# EVB-NORA-B2_SCHEM_0001_Power.net
KiCad netlist of a schematic drawn in Altium Designer
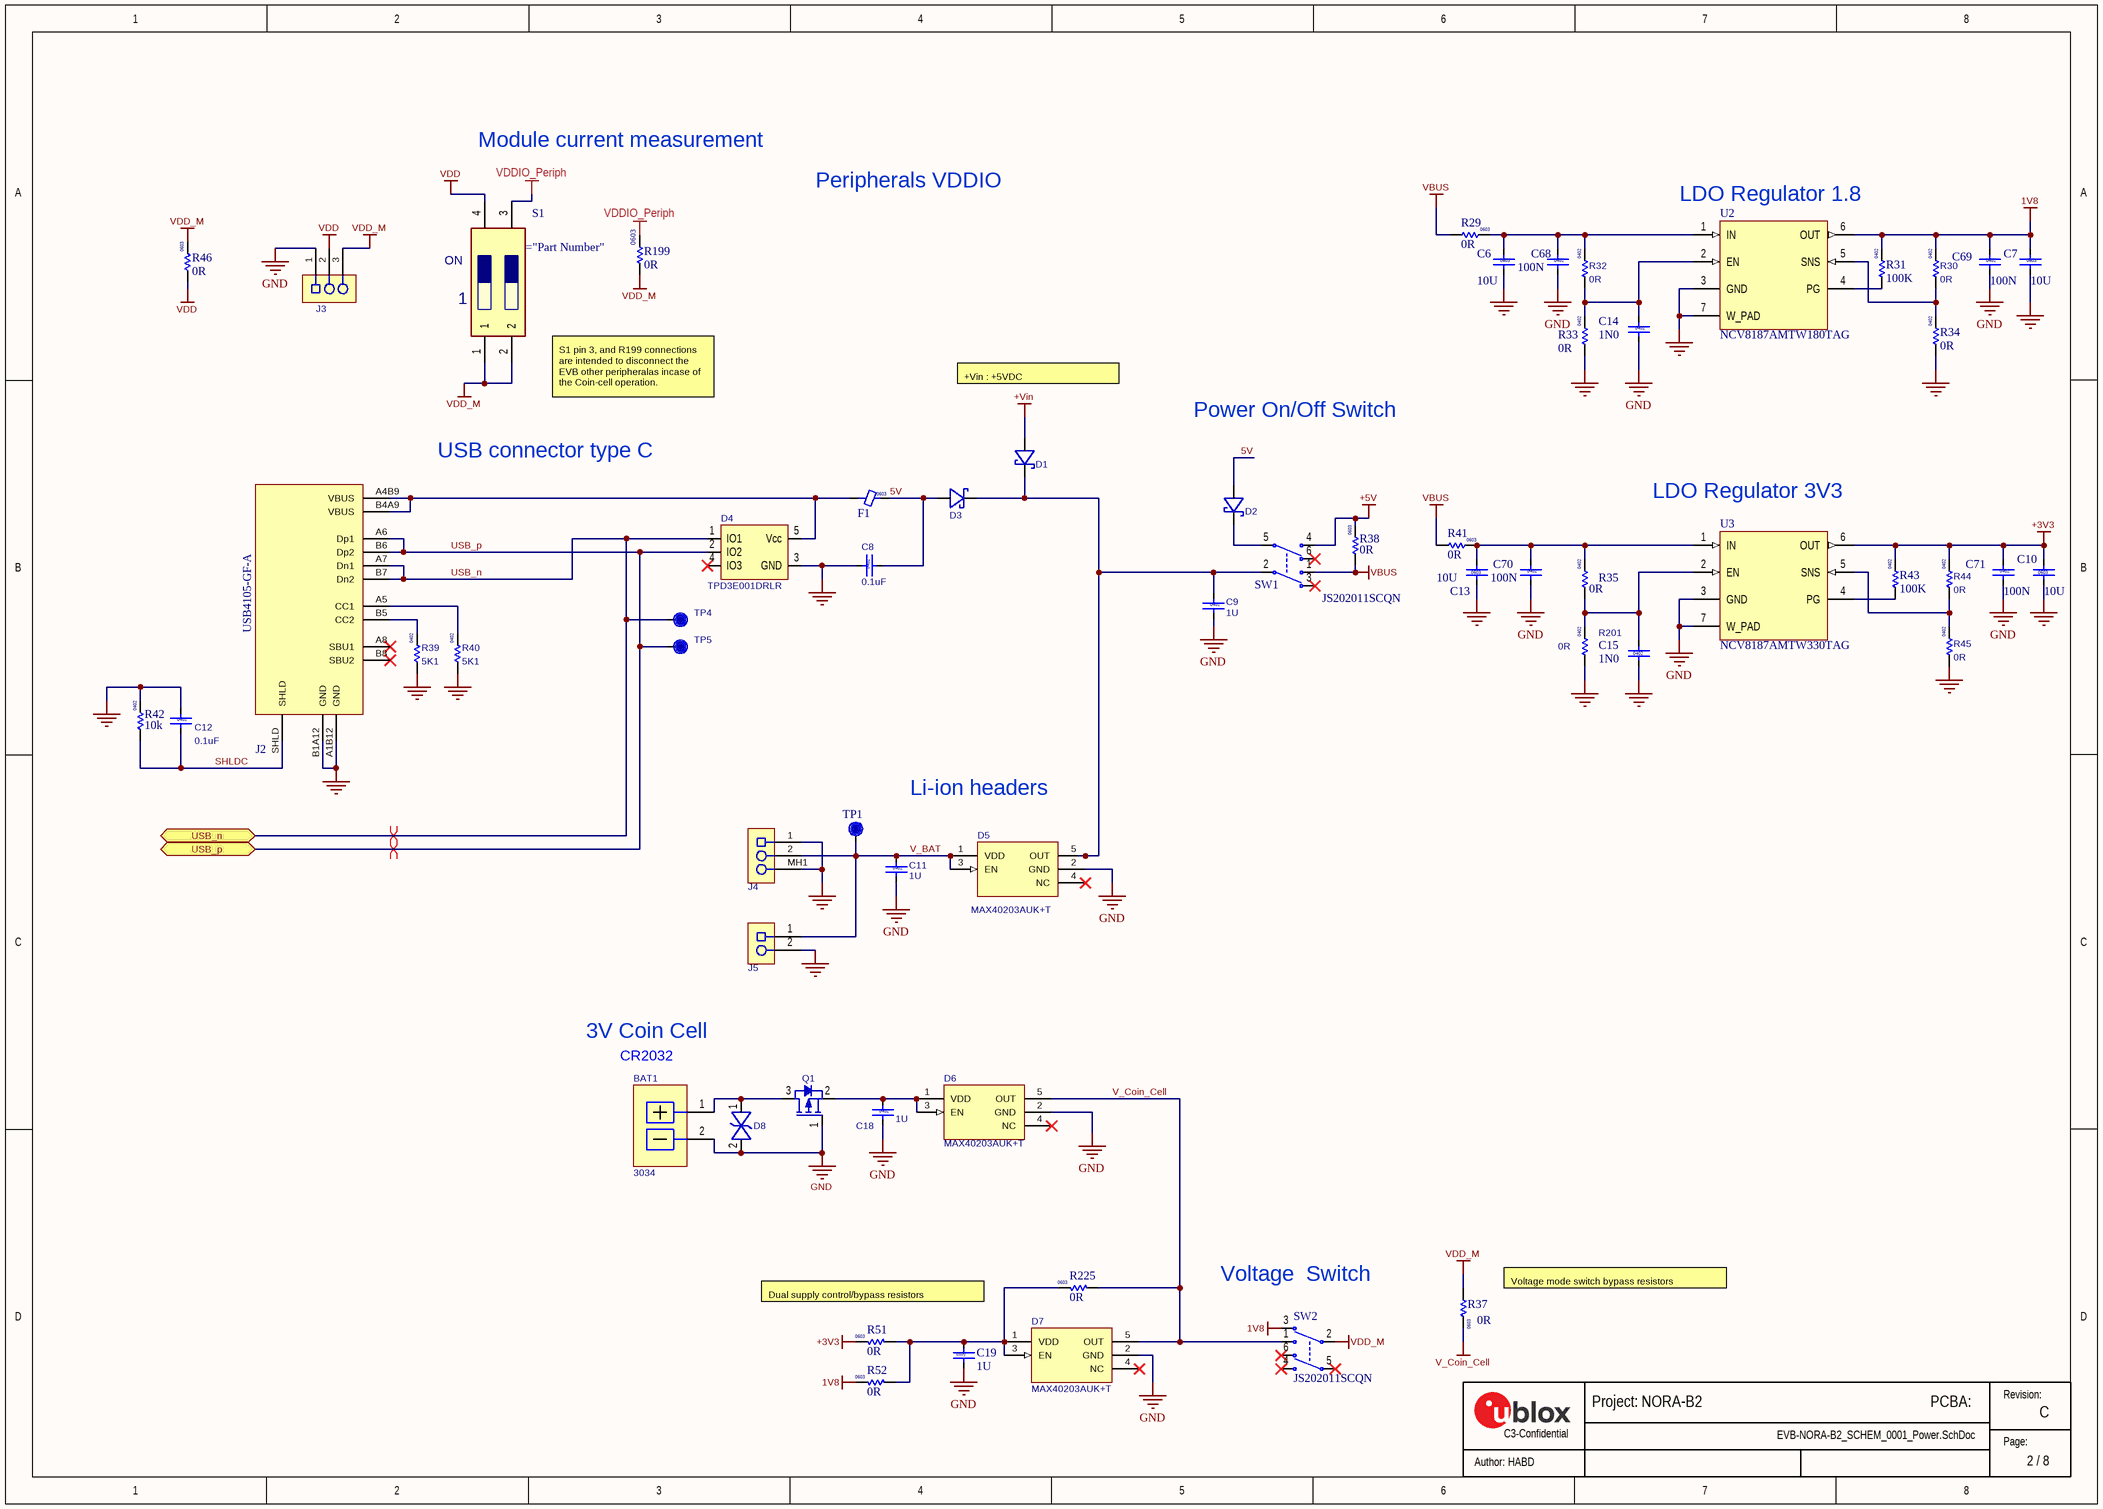
[diagram p0: EVB-NORA-B2_SCHEM_0001_Power.SchDoc]

(export (version "E")
  (design (tool "Eeschema 10.0.6"))
  (components
    (comp (ref "BAT1")
      (value "UBXH03-0000009")
      (footprint "3034")
      (description "BATTERY HOLDER COIN SMT CR2020 CR2025 CR2032 KEYSTONE 3034")
      (fields
        (field (name "MANUFACTURER P/N") "3034")
        (field (name "MANUFACTURER") "Keystone Electronics Corporation")
        (field (name "EDITOR") "eric.moog")
      )
      (libsource (lib "UBX_Parts_DB_Lib") (part "Battery_2Pin"))
    )
    (comp (ref "C6")
      (value "10U")
      (footprint "CAP_0603_1750Lx950Wx850H_600x1000Pad_900G_FLX")
      (description "CAP CER X7R 0603 10U 20% 10V")
      (fields
        (field (name "SIZE") "0603")
        (field (name "PART NUMBER") "UBXH01-0000310")
        (field (name "TOLERANCE") "20%")
        (field (name "EDITOR") "michael.hein")
        (field (name "RELEASED BY") "martin.grasse")
      )
      (libsource (lib "UBX_Parts_DB_Lib") (part "Cap Chip"))
    )
    (comp (ref "C7")
      (value "10U")
      (footprint "CAP_0603_1750Lx950Wx850H_600x1000Pad_900G_FLX")
      (description "CAP CER X7R 0603 10U 20% 10V")
      (fields
        (field (name "SIZE") "0603")
        (field (name "PART NUMBER") "UBXH01-0000310")
        (field (name "TOLERANCE") "20%")
        (field (name "EDITOR") "michael.hein")
        (field (name "RELEASED BY") "martin.grasse")
      )
      (libsource (lib "UBX_Parts_DB_Lib") (part "Cap Chip"))
    )
    (comp (ref "C8")
      (value "0.1uF")
      (footprint "Cap 0402 HD")
      (description "Cap, Ceramic 0.1uF 10V 10% X5R 0402")
      (fields
        (field (name "SIZE") "0402")
        (field (name "PART NUMBER") "120-00016")
        (field (name "MANUFACTURER") "Murata Electronics North America")
      )
      (libsource (lib "Arena_Parts_DB_Lib") (part "Cap Chip"))
    )
    (comp (ref "C9")
      (value "1U")
      (footprint "Cap 0402 HD")
      (description "CAP CER X5R 0402 1U 10% 10V")
      (fields
        (field (name "SIZE") "0402")
        (field (name "PART NUMBER") "UBXH01-0000248")
        (field (name "TOLERANCE") "10%")
        (field (name "EDITOR") "michael.hein")
        (field (name "RELEASED BY") "igor.shevchenko")
      )
      (libsource (lib "UBX_Parts_DB_Lib") (part "Cap Chip"))
    )
    (comp (ref "C10")
      (value "10U")
      (footprint "CAP_0603_1750Lx950Wx850H_600x1000Pad_900G_FLX")
      (description "CAP CER X7R 0603 10U 20% 10V")
      (fields
        (field (name "SIZE") "0603")
        (field (name "PART NUMBER") "UBXH01-0000310")
        (field (name "TOLERANCE") "20%")
        (field (name "EDITOR") "michael.hein")
        (field (name "RELEASED BY") "martin.grasse")
      )
      (libsource (lib "UBX_Parts_DB_Lib") (part "Cap Chip"))
    )
    (comp (ref "C11")
      (value "1U")
      (footprint "Cap 0402 HD")
      (description "CAP CER X5R 0402 1U 10% 10V")
      (fields
        (field (name "SIZE") "0402")
        (field (name "PART NUMBER") "UBXH01-0000248")
        (field (name "TOLERANCE") "10%")
        (field (name "EDITOR") "michael.hein")
        (field (name "RELEASED BY") "igor.shevchenko")
      )
      (libsource (lib "UBX_Parts_DB_Lib") (part "Cap Chip"))
    )
    (comp (ref "C12")
      (value "0.1uF")
      (footprint "Cap 0402 HD")
      (description "Cap, Ceramic 0.1uF 10V 10% X5R 0402")
      (fields
        (field (name "SIZE") "0402")
        (field (name "PART NUMBER") "120-00016")
        (field (name "MANUFACTURER") "Murata Electronics North America")
      )
      (libsource (lib "Arena_Parts_DB_Lib") (part "Cap Chip"))
    )
    (comp (ref "C13")
      (value "10U")
      (footprint "CAP_0603_1750Lx950Wx850H_600x1000Pad_900G_FLX")
      (description "CAP CER X7R 0603 10U 20% 10V")
      (fields
        (field (name "SIZE") "0603")
        (field (name "PART NUMBER") "UBXH01-0000310")
        (field (name "TOLERANCE") "20%")
        (field (name "EDITOR") "michael.hein")
        (field (name "RELEASED BY") "martin.grasse")
      )
      (libsource (lib "UBX_Parts_DB_Lib") (part "Cap Chip"))
    )
    (comp (ref "C14")
      (value "1N0")
      (footprint "Cap 0402 HD")
      (description "CAP CER X7R 0402 1N0 10% 50V")
      (fields
        (field (name "SIZE") "0402")
        (field (name "PART NUMBER") "UBXH01-0000013")
        (field (name "TOLERANCE") "10%")
        (field (name "EDITOR") "massimo.vlacci")
        (field (name "RELEASED BY") "dario.antonaz")
      )
      (libsource (lib "UBX_Parts_DB_Lib") (part "Cap Chip"))
    )
    (comp (ref "C15")
      (value "1N0")
      (footprint "Cap 0402 HD")
      (description "CAP CER X7R 0402 1N0 10% 50V")
      (fields
        (field (name "SIZE") "0402")
        (field (name "PART NUMBER") "UBXH01-0000013")
        (field (name "TOLERANCE") "10%")
        (field (name "EDITOR") "massimo.vlacci")
        (field (name "RELEASED BY") "dario.antonaz")
      )
      (libsource (lib "UBX_Parts_DB_Lib") (part "Cap Chip"))
    )
    (comp (ref "C18")
      (value "1U")
      (footprint "Cap 0402 HD")
      (description "CAP CER X5R 0402 1U 10% 10V")
      (fields
        (field (name "SIZE") "0402")
        (field (name "PART NUMBER") "UBXH01-0000248")
        (field (name "TOLERANCE") "10%")
        (field (name "EDITOR") "michael.hein")
        (field (name "RELEASED BY") "igor.shevchenko")
      )
      (libsource (lib "UBX_Parts_DB_Lib") (part "Cap Chip"))
    )
    (comp (ref "C19")
      (value "1U")
      (footprint "Cap 0402 HD")
      (description "CAP CER X5R 0402 1U 10% 10V")
      (fields
        (field (name "PART NUMBER") "UBXH01-0000248")
        (field (name "TOLERANCE") "10%")
        (field (name "CASE/PACKAGE") "0x0y")
        (field (name "EDITOR") "michael.hein")
        (field (name "RELEASED BY") "igor.shevchenko")
      )
      (libsource (lib "UBX_Parts_DB_Lib") (part "Cap Chip"))
    )
    (comp (ref "C68")
      (value "100N")
      (description "CAP CER X5R 0402 100N 10% 50V")
      (fields
        (field (name "CASE/PACKAGE") "0402")
        (field (name "PART NUMBER") "UBXH01-0000204")
        (field (name "TOLERANCE") "10%")
        (field (name "OWNER") "Matej Budin")
      )
      (libsource (lib "UBX_Arena") (part "Cap Chip"))
    )
    (comp (ref "C69")
      (value "100N")
      (description "CAP CER X5R 0402 100N 10% 50V")
      (fields
        (field (name "CASE/PACKAGE") "0402")
        (field (name "PART NUMBER") "UBXH01-0000204")
        (field (name "TOLERANCE") "10%")
        (field (name "OWNER") "Matej Budin")
      )
      (libsource (lib "UBX_Arena") (part "Cap Chip"))
    )
    (comp (ref "C70")
      (value "100N")
      (description "CAP CER X5R 0402 100N 10% 50V")
      (fields
        (field (name "CASE/PACKAGE") "0402")
        (field (name "PART NUMBER") "UBXH01-0000204")
        (field (name "TOLERANCE") "10%")
        (field (name "OWNER") "Matej Budin")
      )
      (libsource (lib "UBX_Arena") (part "Cap Chip"))
    )
    (comp (ref "C71")
      (value "100N")
      (description "CAP CER X5R 0402 100N 10% 50V")
      (fields
        (field (name "CASE/PACKAGE") "0402")
        (field (name "PART NUMBER") "UBXH01-0000204")
        (field (name "TOLERANCE") "10%")
        (field (name "OWNER") "Matej Budin")
      )
      (libsource (lib "UBX_Arena") (part "Cap Chip"))
    )
    (comp (ref "D1")
      (value "110-00005")
      (footprint "SOD-123F_U")
      (description "Diode, Schottky, 20V 1A SOD-123F, 340mV Vf @ 1A\nMBR120VLSFT3G")
      (fields (field (name "VOLTAGE") "20V"))
      (libsource (lib "Arena_Parts_DB_Lib") (part "Diode_Schottky"))
    )
    (comp (ref "D2")
      (value "110-00005")
      (footprint "SOD-123F_U")
      (description "Diode, Schottky, 20V 1A SOD-123F, 340mV Vf @ 1A\nMBR120VLSFT3G")
      (fields (field (name "VOLTAGE") "20V"))
      (libsource (lib "Arena_Parts_DB_Lib") (part "Diode_Schottky"))
    )
    (comp (ref "D3")
      (value "110-00005")
      (footprint "SOD-123F_U")
      (description "Diode, Schottky, 20V 1A SOD-123F, 340mV Vf @ 1A\nMBR120VLSFT3G")
      (fields (field (name "VOLTAGE") "20V"))
      (libsource (lib "Arena_Parts_DB_Lib") (part "Diode_Schottky"))
    )
    (comp (ref "D4")
      (value "110-00018")
      (footprint "SOT-553")
      (description "LOW-CAPACITANCE 3-CHANNEL ESD-PROTECTION ARRAY")
      (fields
        (field (name "MANUFACTURER P/N") "TPD3E001DRLR")
        (field (name "MANUFACTURER") "Texas Instruments")
        (field (name "VOLTAGE") "5V")
      )
      (libsource (lib "Arena_Parts_DB_Lib") (part "TPD3E001"))
    )
    (comp (ref "D5")
      (value "UBXH12-0000539")
      (footprint "SOT-23-5_2")
      (description "IDEAL DIODE OR CONTROLLER SOURCE SELECTOR SWITCH P-CHANNEL 1:1 SOT-23-5 5.5V 1A")
      (fields
        (field (name "VOLTAGE") "5.5V")
        (field (name "MANUFACTURER PART NUMBER 1") "MAX40203AUK+T")
        (field (name "MANUFACTURER") "Maxim")
        (field (name "EDITOR") "eric.moog")
      )
      (libsource (lib "UBX_Parts_DB_Lib") (part "MAX40203AUK"))
    )
    (comp (ref "D6")
      (value "UBXH12-0000539")
      (footprint "SOT-23-5_2")
      (description "IDEAL DIODE OR CONTROLLER SOURCE SELECTOR SWITCH P-CHANNEL 1:1 SOT-23-5 5.5V 1A")
      (fields
        (field (name "VOLTAGE") "5.5V")
        (field (name "MANUFACTURER PART NUMBER 1") "MAX40203AUK+T")
        (field (name "MANUFACTURER") "Maxim")
        (field (name "EDITOR") "eric.moog")
      )
      (libsource (lib "UBX_Parts_DB_Lib") (part "MAX40203AUK"))
    )
    (comp (ref "D7")
      (value "UBXH12-0000539")
      (footprint "SOT-23-5_2")
      (description "IDEAL DIODE OR CONTROLLER SOURCE SELECTOR SWITCH P-CHANNEL 1:1 SOT-23-5 5.5V 1A")
      (fields
        (field (name "VOLTAGE") "5.5V")
        (field (name "MANUFACTURER PART NUMBER 1") "MAX40203AUK+T")
        (field (name "MANUFACTURER") "Maxim")
        (field (name "EDITOR") "eric.moog")
      )
      (libsource (lib "UBX_Parts_DB_Lib") (part "MAX40203AUK"))
    )
    (comp (ref "D8")
      (value "UBXH07-0000034")
      (footprint "SOD-923")
      (description "ESD PROTECTION DIODE ULTRA LOW LEAKAGE SOD923 ON SEMI 3V3")
      (fields
        (field (name "MANUFACTURER") "ON Semiconductor")
        (field (name "EDITOR") "pierpaolo.arban")
        (field (name "RELEASED BY") "dario.antonaz")
      )
      (libsource (lib "UBX_Parts_DB_Lib") (part "Diode_TVS"))
    )
    (comp (ref "F1")
      (value "UBXH08-0000001")
      (footprint "IND_0603_1750Lx950Wx1050H_600x800Pad_800G_FLX")
      (description "FERRITE BEAD 0603 600 OHM AT 100MHZ 600OHM 500mA")
      (fields
        (field (name "SIZE") "0603")
        (field (name "MANUFACTURER") "TDK Corporation")
        (field (name "EDITOR") "daniel.hurni")
        (field (name "RELEASED BY") "martin.frauchiger")
      )
      (libsource (lib "UBX_Parts_DB_Lib") (part "FB sm"))
    )
    (comp (ref "J2")
      (value "USB4105-GF-A")
      (footprint "USB4105-GF-A")
      (description "CONN RCP USB2.0 TYP C 24P SMD RA 20V 6.25A")
      (fields
        (field (name "PART NUMBER") "UBXH04-0000785")
        (field (name "VOLTAGE") "<20V DC")
        (field (name "EDITOR") "eric.moog")
      )
      (libsource (lib "UBX_Parts_DB_Lib") (part "USB4105-GF-A"))
    )
    (comp (ref "J3")
      (value "UBXH04-0000792")
      (footprint "HDR-0.1P-3Pin-1Row-SMT")
      (description "1-ROW SMD CONN 100MIL GRID 3 -PIN 100V 3A")
      (fields (field (name "MANUFACTURER") "HARWiN") (field (name "EDITOR") "eric.moog"))
      (libsource (lib "UBX_Parts_DB_Lib") (part "CON-3Pin_1Row"))
    )
    (comp (ref "J4")
      (value "UBXH04-0000791")
      (footprint "B2B-PH-SM4-TB")
      (description "CONN 1-ROW SMT 2.0MM GRID 2-PIN VERT 100V 2A")
      (fields
        (field (name "VOLTAGE") "None")
        (field (name "MANUFACTURER") "JST")
        (field (name "EDITOR") "eric.moog")
      )
      (libsource (lib "UBX_Parts_DB_Lib") (part "CON-2Pin_1Row_W-MH"))
    )
    (comp (ref "J5")
      (value "UBXH04-0000026")
      (footprint "HDR-0.1P-2PIN-TH")
      (description "1-ROW TH-PCB SOCKETS 100MIL GRID 2-PIN 0.64MM SQUARE POLARIZE")
      (fields
        (field (name "MANUFACTURER") "HARWiN")
        (field (name "EDITOR") "roland.rust")
        (field (name "RELEASED BY") "alvaro.nussbaum")
      )
      (libsource (lib "UBX_Parts_DB_Lib") (part "CON-2Pin_1Row"))
    )
    (comp (ref "Q1")
      (value "140-00005")
      (footprint "SOT-723")
      (description "P-MOSFET, 20V, 100mA, SOT-723-3")
      (fields (field (name "VOLTAGE") "20V"))
      (libsource (lib "Arena_Parts_DB_Lib") (part "MOSFET-P"))
    )
    (comp (ref "R29")
      (value "0R")
      (footprint "RES_0603_1700Lx950Wx600H_600x1000Pad_800G_FLX")
      (description "RES THICK FILM CHIP 0603 0R 0 100mW")
      (fields
        (field (name "SIZE") "0603")
        (field (name "PART NUMBER") "UBXH18-0003001")
        (field (name "TOLERANCE") "0")
        (field (name "EDITOR") "martin.frauchiger")
        (field (name "RELEASED BY") "martin.frauchiger")
      )
      (libsource (lib "UBX_Parts_DB_Lib") (part "Res sm"))
    )
    (comp (ref "R30")
      (value "0R")
      (footprint "RES 0402 HD")
      (description "RES THICK FILM CHIP 0402 0R 0 100mW")
      (fields
        (field (name "SIZE") "0402")
        (field (name "PART NUMBER") "UBXH18-0003002")
        (field (name "TOLERANCE") "0")
        (field (name "EDITOR") "charlotte.biber")
        (field (name "RELEASED BY") "peter.mueller")
      )
      (libsource (lib "UBX_Parts_DB_Lib") (part "Res sm"))
    )
    (comp (ref "R31")
      (value "100K")
      (footprint "RES 0402 HD")
      (description "RES THICK FILM CHIP 0402 100K 1% 63mW")
      (fields
        (field (name "SIZE") "0402")
        (field (name "PART NUMBER") "UBXH18-0000005")
        (field (name "TOLERANCE") "1%")
        (field (name "EDITOR") "dario.antonaz")
        (field (name "RELEASED BY") "sandro.sestan")
      )
      (libsource (lib "UBX_Parts_DB_Lib") (part "Res sm"))
    )
    (comp (ref "R32")
      (value "0R")
      (footprint "RES 0402 HD")
      (description "RES THICK FILM CHIP 0402 0R 0 100mW")
      (fields
        (field (name "SIZE") "0402")
        (field (name "PART NUMBER") "UBXH18-0003002")
        (field (name "TOLERANCE") "0")
        (field (name "EDITOR") "charlotte.biber")
        (field (name "RELEASED BY") "peter.mueller")
      )
      (libsource (lib "UBX_Parts_DB_Lib") (part "Res sm"))
    )
    (comp (ref "R33")
      (value "0R")
      (footprint "RES 0402 HD")
      (description "RES THICK FILM CHIP 0402 0R 0 100mW")
      (fields
        (field (name "SIZE") "0402")
        (field (name "PART NUMBER") "UBXH18-0003002")
        (field (name "TOLERANCE") "0")
        (field (name "EDITOR") "charlotte.biber")
        (field (name "RELEASED BY") "peter.mueller")
      )
      (libsource (lib "UBX_Parts_DB_Lib") (part "Res sm"))
    )
    (comp (ref "R34")
      (value "0R")
      (footprint "RES 0402 HD")
      (description "RES THICK FILM CHIP 0402 0R 0 100mW")
      (fields
        (field (name "SIZE") "0402")
        (field (name "PART NUMBER") "UBXH18-0003002")
        (field (name "TOLERANCE") "0")
        (field (name "EDITOR") "charlotte.biber")
        (field (name "RELEASED BY") "peter.mueller")
      )
      (libsource (lib "UBX_Parts_DB_Lib") (part "Res sm"))
    )
    (comp (ref "R35")
      (value "0R")
      (footprint "RES 0402 HD")
      (description "RES THICK FILM CHIP 0402 0R 0 100mW")
      (fields
        (field (name "SIZE") "0402")
        (field (name "PART NUMBER") "UBXH18-0003002")
        (field (name "TOLERANCE") "0")
        (field (name "EDITOR") "charlotte.biber")
        (field (name "RELEASED BY") "peter.mueller")
      )
      (libsource (lib "UBX_Parts_DB_Lib") (part "Res sm"))
    )
    (comp (ref "R37")
      (value "0R")
      (footprint "RES_0603_1700Lx950Wx600H_600x1000Pad_800G_FLX")
      (description "RES THICK FILM CHIP 0603 0R 0 100mW")
      (fields
        (field (name "SIZE") "0603")
        (field (name "PART NUMBER") "UBXH18-0003001")
        (field (name "TOLERANCE") "0")
        (field (name "EDITOR") "martin.frauchiger")
        (field (name "RELEASED BY") "martin.frauchiger")
      )
      (libsource (lib "UBX_Parts_DB_Lib") (part "Res sm"))
    )
    (comp (ref "R38")
      (value "0R")
      (footprint "RES_0603_1700Lx950Wx600H_600x1000Pad_800G_FLX")
      (description "RES THICK FILM CHIP 0603 0R 0 100mW")
      (fields
        (field (name "SIZE") "0603")
        (field (name "PART NUMBER") "UBXH18-0003001")
        (field (name "TOLERANCE") "0")
        (field (name "EDITOR") "martin.frauchiger")
        (field (name "RELEASED BY") "martin.frauchiger")
      )
      (libsource (lib "UBX_Parts_DB_Lib") (part "Res sm"))
    )
    (comp (ref "R39")
      (value "5K1")
      (footprint "RES 0402 HD")
      (description "RES THICK FILM CHIP 0402 5K1 5% 100mW")
      (fields
        (field (name "SIZE") "0402")
        (field (name "PART NUMBER") "UBXH18-0008066")
        (field (name "TOLERANCE") "5%")
        (field (name "EDITOR") "alvaro.nussbaum")
        (field (name "RELEASED BY") "roland.rust")
      )
      (libsource (lib "UBX_Parts_DB_Lib") (part "Res sm"))
    )
    (comp (ref "R40")
      (value "5K1")
      (footprint "RES 0402 HD")
      (description "RES THICK FILM CHIP 0402 5K1 5% 100mW")
      (fields
        (field (name "SIZE") "0402")
        (field (name "PART NUMBER") "UBXH18-0008066")
        (field (name "TOLERANCE") "5%")
        (field (name "EDITOR") "alvaro.nussbaum")
        (field (name "RELEASED BY") "roland.rust")
      )
      (libsource (lib "UBX_Parts_DB_Lib") (part "Res sm"))
    )
    (comp (ref "R41")
      (value "0R")
      (footprint "RES_0603_1700Lx950Wx600H_600x1000Pad_800G_FLX")
      (description "RES THICK FILM CHIP 0603 0R 0 100mW")
      (fields
        (field (name "SIZE") "0603")
        (field (name "PART NUMBER") "UBXH18-0003001")
        (field (name "TOLERANCE") "0")
        (field (name "EDITOR") "martin.frauchiger")
        (field (name "RELEASED BY") "martin.frauchiger")
      )
      (libsource (lib "UBX_Parts_DB_Lib") (part "Res sm"))
    )
    (comp (ref "R42")
      (value "10k")
      (footprint "RES 0402 HD")
      (description "Resistor 10k ohm 1% 1/16W, 0402")
      (fields
        (field (name "SIZE") "0402")
        (field (name "PART NUMBER") "180-00024")
        (field (name "POWER") "1/16W")
      )
      (libsource (lib "Arena_Parts_DB_Lib") (part "Res sm"))
    )
    (comp (ref "R43")
      (value "100K")
      (footprint "RES 0402 HD")
      (description "RES THICK FILM CHIP 0402 100K 1% 63mW")
      (fields
        (field (name "SIZE") "0402")
        (field (name "PART NUMBER") "UBXH18-0000005")
        (field (name "TOLERANCE") "1%")
        (field (name "EDITOR") "dario.antonaz")
        (field (name "RELEASED BY") "sandro.sestan")
      )
      (libsource (lib "UBX_Parts_DB_Lib") (part "Res sm"))
    )
    (comp (ref "R44")
      (value "0R")
      (footprint "RES 0402 HD")
      (description "RES THICK FILM CHIP 0402 0R 0 100mW")
      (fields
        (field (name "SIZE") "0402")
        (field (name "PART NUMBER") "UBXH18-0003002")
        (field (name "TOLERANCE") "0")
        (field (name "EDITOR") "charlotte.biber")
        (field (name "RELEASED BY") "peter.mueller")
      )
      (libsource (lib "UBX_Parts_DB_Lib") (part "Res sm"))
    )
    (comp (ref "R45")
      (value "0R")
      (footprint "RES 0402 HD")
      (description "RES THICK FILM CHIP 0402 0R 0 100mW")
      (fields
        (field (name "SIZE") "0402")
        (field (name "PART NUMBER") "UBXH18-0003002")
        (field (name "TOLERANCE") "0")
        (field (name "EDITOR") "charlotte.biber")
        (field (name "RELEASED BY") "peter.mueller")
      )
      (libsource (lib "UBX_Parts_DB_Lib") (part "Res sm"))
    )
    (comp (ref "R46")
      (value "0R")
      (footprint "RES_0603_1700Lx950Wx600H_600x1000Pad_800G_FLX")
      (description "RES THICK FILM CHIP 0603 0R 0 100mW")
      (fields
        (field (name "SIZE") "0603")
        (field (name "PART NUMBER") "UBXH18-0003001")
        (field (name "TOLERANCE") "0")
        (field (name "EDITOR") "martin.frauchiger")
        (field (name "RELEASED BY") "martin.frauchiger")
      )
      (libsource (lib "UBX_Parts_DB_Lib") (part "Res sm"))
    )
    (comp (ref "R51")
      (value "0R")
      (footprint "RES_0603_1700Lx950Wx600H_600x1000Pad_800G_FLX")
      (description "RES THICK FILM CHIP 0603 0R 0 100mW")
      (fields
        (field (name "SIZE") "0603")
        (field (name "PART NUMBER") "UBXH18-0003001")
        (field (name "TOLERANCE") "0")
        (field (name "EDITOR") "martin.frauchiger")
        (field (name "RELEASED BY") "martin.frauchiger")
      )
      (libsource (lib "UBX_Parts_DB_Lib") (part "Res sm"))
    )
    (comp (ref "R52")
      (value "0R")
      (footprint "RES_0603_1700Lx950Wx600H_600x1000Pad_800G_FLX")
      (description "RES THICK FILM CHIP 0603 0R 0 100mW")
      (fields
        (field (name "SIZE") "0603")
        (field (name "PART NUMBER") "UBXH18-0003001")
        (field (name "TOLERANCE") "0")
        (field (name "EDITOR") "martin.frauchiger")
        (field (name "RELEASED BY") "martin.frauchiger")
      )
      (libsource (lib "UBX_Parts_DB_Lib") (part "Res sm"))
    )
    (comp (ref "R199")
      (value "0R")
      (footprint "RES_0603_1700Lx950Wx600H_600x1000Pad_800G_FLX")
      (description "RES THICK FILM CHIP 0603 0R 0 100mW")
      (fields
        (field (name "SIZE") "0603")
        (field (name "PART NUMBER") "UBXH18-0003001")
        (field (name "TOLERANCE") "0")
        (field (name "EDITOR") "martin.frauchiger")
        (field (name "RELEASED BY") "martin.frauchiger")
      )
      (libsource (lib "UBX_Parts_DB_Lib") (part "Res sm"))
    )
    (comp (ref "R201")
      (value "0R")
      (footprint "RES 0402 HD")
      (description "RES THICK FILM CHIP 0402 0R 0 100mW")
      (fields
        (field (name "SIZE") "0402")
        (field (name "PART NUMBER") "UBXH18-0003002")
        (field (name "TOLERANCE") "0")
        (field (name "EDITOR") "charlotte.biber")
        (field (name "RELEASED BY") "peter.mueller")
      )
      (libsource (lib "UBX_Parts_DB_Lib") (part "Res sm"))
    )
    (comp (ref "R225")
      (value "0R")
      (footprint "RES_0603_1700Lx950Wx600H_600x1000Pad_800G_FLX")
      (description "RES THICK FILM CHIP 0603 0R 0 100mW")
      (fields
        (field (name "SIZE") "0603")
        (field (name "PART NUMBER") "UBXH18-0003001")
        (field (name "TOLERANCE") "0")
        (field (name "EDITOR") "martin.frauchiger")
        (field (name "RELEASED BY") "martin.frauchiger")
      )
      (libsource (lib "UBX_Parts_DB_Lib") (part "Res sm"))
    )
    (comp (ref "S1")
      (value "~")
      (footprint "2182LPSTJ")
      (description "Switch")
      (fields
        (field (name "MANUFACTURER_PART_NUMBER") "218-2LPSTJ")
        (field (name "MOUSER PART NUMBER") "774-2182LPSTJ")
      )
      (libsource (lib "SamacSys") (part "218-2LPSTJ"))
    )
    (comp (ref "SW1")
      (value "UBXH19-0000050")
      (footprint "SW_Slide_DPDT_JS202011SCQN")
      (description "2 WAY ON-ON SUB-MINIATURE SLIDE SWITCH SMD JS SERIES")
      (fields
        (field (name "MANUFACTURER P/N") "JS202011SCQN")
        (field (name "MANUFACTURER") "C&K Components")
        (field (name "EDITOR") "andre.pick")
        (field (name "RELEASED BY") "martin.pilik")
      )
      (libsource (lib "UBX_Parts_DB_Lib") (part "SW_DPDT_JS2020"))
    )
    (comp (ref "SW2")
      (value "UBXH19-0000050")
      (footprint "SW_Slide_DPDT_JS202011SCQN")
      (description "2 WAY ON-ON SUB-MINIATURE SLIDE SWITCH SMD JS SERIES")
      (fields
        (field (name "MANUFACTURER P/N") "JS202011SCQN")
        (field (name "MANUFACTURER") "C&K Components")
        (field (name "EDITOR") "andre.pick")
        (field (name "RELEASED BY") "martin.pilik")
      )
      (libsource (lib "UBX_Parts_DB_Lib") (part "SW_DPDT_JS2020"))
    )
    (comp (ref "TP1")
      (value "TP10R")
      (footprint "TP10R")
      (description "Testpoint, Round 1.0mm Dia")
      (fields (field (name "ADDED BY") "Jeremy D") (field (name "CHECKED BY") "Paul B"))
      (libsource (lib "") (part "TP_R_1"))
    )
    (comp (ref "TP4")
      (value "TP10R")
      (footprint "TP10R")
      (description "Testpoint, Round 1.0mm Dia")
      (fields (field (name "ADDED BY") "Jeremy D") (field (name "CHECKED BY") "Paul B"))
      (libsource (lib "LEGACY_Rigado_AltiumLib") (part "TP_R"))
    )
    (comp (ref "TP5")
      (value "TP10R")
      (footprint "TP10R")
      (description "Testpoint, Round 1.0mm Dia")
      (fields (field (name "ADDED BY") "Jeremy D") (field (name "CHECKED BY") "Paul B"))
      (libsource (lib "LEGACY_Rigado_AltiumLib") (part "TP_R"))
    )
    (comp (ref "U2")
      (value "UBXH43-0000004")
      (footprint "DFN0.65P-6Pin_W-Pad")
      (description "LDO REGULATOR 1.8V,LOW Iq, WDFNW6 2x2 MM PACKAGE 1200 mA")
      (fields
        (field (name "MANUFACTURER PART NUMBER 1") "NCV8187AMTW180TAG")
        (field (name "OWNER") "Hozaifa Abdelgadir")
      )
      (libsource (lib "UBX_Arena") (part "NCV8187"))
    )
    (comp (ref "U3")
      (value "UBXH43-0000003")
      (footprint "DFN0.65P-6Pin_W-Pad")
      (description "LDO REGULATOR 3.3V,LOW Iq, WDFNW6 2x2 MM, 0.65P PACKAGE 1200 mA")
      (fields
        (field (name "MANUFACTURER PART NUMBER 1") "NCV8187AMTW330TAG")
        (field (name "OWNER") "Hozaifa Abdelgadir")
      )
      (libsource (lib "UBX_Arena") (part "NCV8187"))
    )
  )
  (nets
    (net (code "1") (name "+3V3") (class "Default")
      (node (ref "C10") (pin "1") (pinfunction "1_1") (pintype "passive"))
      (node (ref "C71") (pin "1") (pinfunction "1_1") (pintype "passive"))
      (node (ref "R43") (pin "2") (pinfunction "2_2") (pintype "passive"))
      (node (ref "R44") (pin "2") (pinfunction "2_2") (pintype "passive"))
      (node (ref "R51") (pin "2") (pinfunction "2_2") (pintype "passive"))
      (node (ref "U3") (pin "6") (pinfunction "OUT_6") (pintype "output"))
    )
    (net (code "2") (name "+5V") (class "Default")
      (node (ref "R38") (pin "2") (pinfunction "2_2") (pintype "passive"))
      (node (ref "SW1") (pin "4") (pinfunction "N.O-2_4") (pintype "passive"))
    )
    (net (code "3") (name "+Vin") (class "Default")
      (node (ref "D1") (pin "A") (pinfunction "Anode_A") (pintype "passive"))
    )
    (net (code "4") (name "/5V") (class "Default")
      (node (ref "C8") (pin "2") (pinfunction "2_2") (pintype "passive"))
      (node (ref "D2") (pin "A") (pinfunction "Anode_A") (pintype "passive"))
      (node (ref "D3") (pin "A") (pinfunction "Anode_A") (pintype "passive"))
      (node (ref "F1") (pin "2") (pinfunction "2_2") (pintype "passive"))
    )
    (net (code "5") (name "/SHLDC") (class "Default")
      (node (ref "C12") (pin "2") (pinfunction "2_2") (pintype "passive"))
      (node (ref "J2") (pin "SHLD") (pinfunction "SHLD_SHLD") (pintype "power_in"))
      (node (ref "R42") (pin "1") (pinfunction "1_1") (pintype "passive"))
    )
    (net (code "6") (name "/USB_n") (class "Default")
      (node (ref "D4") (pin "1") (pinfunction "IO1_1") (pintype "passive"))
      (node (ref "J2") (pin "A7") (pinfunction "Dn1_A7") (pintype "power_in"))
      (node (ref "J2") (pin "B7") (pinfunction "Dn2_B7") (pintype "power_in"))
      (node (ref "TP4") (pin "1") (pintype "passive"))
    )
    (net (code "7") (name "/USB_p") (class "Default")
      (node (ref "D4") (pin "2") (pinfunction "IO2_2") (pintype "passive"))
      (node (ref "J2") (pin "A6") (pinfunction "Dp1_A6") (pintype "power_in"))
      (node (ref "J2") (pin "B6") (pinfunction "Dp2_B6") (pintype "power_in"))
      (node (ref "TP5") (pin "1") (pintype "passive"))
    )
    (net (code "8") (name "/V_BAT") (class "Default")
      (node (ref "C11") (pin "1") (pinfunction "1_1") (pintype "passive"))
      (node (ref "D5") (pin "1") (pinfunction "VDD_1") (pintype "power_in"))
      (node (ref "D5") (pin "3") (pinfunction "EN_3") (pintype "input"))
      (node (ref "J4") (pin "2") (pinfunction "2_2") (pintype "passive"))
      (node (ref "J5") (pin "1") (pinfunction "1_1") (pintype "passive"))
      (node (ref "TP1") (pin "1") (pintype "passive"))
    )
    (net (code "9") (name "1V8") (class "Default")
      (node (ref "C69") (pin "1") (pinfunction "1_1") (pintype "passive"))
      (node (ref "C7") (pin "1") (pinfunction "1_1") (pintype "passive"))
      (node (ref "R30") (pin "2") (pinfunction "2_2") (pintype "passive"))
      (node (ref "R31") (pin "2") (pinfunction "2_2") (pintype "passive"))
      (node (ref "R52") (pin "2") (pinfunction "2_2") (pintype "passive"))
      (node (ref "SW2") (pin "3") (pinfunction "N.C-1_3") (pintype "passive"))
      (node (ref "U2") (pin "6") (pinfunction "OUT_6") (pintype "output"))
    )
    (net (code "10") (name "GND") (class "Default")
      (node (ref "BAT1") (pin "2") (pinfunction "2_2") (pintype "power_in"))
      (node (ref "C10") (pin "2") (pinfunction "2_2") (pintype "passive"))
      (node (ref "C11") (pin "2") (pinfunction "2_2") (pintype "passive"))
      (node (ref "C12") (pin "1") (pinfunction "1_1") (pintype "passive"))
      (node (ref "C13") (pin "2") (pinfunction "2_2") (pintype "passive"))
      (node (ref "C14") (pin "2") (pinfunction "2_2") (pintype "passive"))
      (node (ref "C15") (pin "1") (pinfunction "1_1") (pintype "passive"))
      (node (ref "C18") (pin "2") (pinfunction "2_2") (pintype "passive"))
      (node (ref "C19") (pin "2") (pinfunction "2_2") (pintype "passive"))
      (node (ref "C6") (pin "2") (pinfunction "2_2") (pintype "passive"))
      (node (ref "C68") (pin "2") (pinfunction "2_2") (pintype "passive"))
      (node (ref "C69") (pin "2") (pinfunction "2_2") (pintype "passive"))
      (node (ref "C7") (pin "2") (pinfunction "2_2") (pintype "passive"))
      (node (ref "C70") (pin "2") (pinfunction "2_2") (pintype "passive"))
      (node (ref "C71") (pin "2") (pinfunction "2_2") (pintype "passive"))
      (node (ref "C8") (pin "1") (pinfunction "1_1") (pintype "passive"))
      (node (ref "C9") (pin "2") (pinfunction "2_2") (pintype "passive"))
      (node (ref "D4") (pin "3") (pinfunction "GND_3") (pintype "power_in"))
      (node (ref "D5") (pin "2") (pinfunction "GND_2") (pintype "power_in"))
      (node (ref "D6") (pin "2") (pinfunction "GND_2") (pintype "power_in"))
      (node (ref "D7") (pin "2") (pinfunction "GND_2") (pintype "power_in"))
      (node (ref "D8") (pin "2") (pintype "passive"))
      (node (ref "J2") (pin "A1B12") (pinfunction "GND_A1B12") (pintype "power_in"))
      (node (ref "J2") (pin "B1A12") (pinfunction "GND_B1A12") (pintype "power_in"))
      (node (ref "J3") (pin "1") (pinfunction "1_1") (pintype "passive"))
      (node (ref "J4") (pin "1") (pinfunction "1_1") (pintype "passive"))
      (node (ref "J4") (pin "MH1") (pinfunction "MH1_MH1") (pintype "passive"))
      (node (ref "J5") (pin "2") (pinfunction "2_2") (pintype "passive"))
      (node (ref "Q1") (pin "1") (pinfunction "G_1") (pintype "passive"))
      (node (ref "R201") (pin "1") (pinfunction "1_1") (pintype "passive"))
      (node (ref "R33") (pin "1") (pinfunction "1_1") (pintype "passive"))
      (node (ref "R34") (pin "1") (pinfunction "1_1") (pintype "passive"))
      (node (ref "R39") (pin "1") (pinfunction "1_1") (pintype "passive"))
      (node (ref "R40") (pin "1") (pinfunction "1_1") (pintype "passive"))
      (node (ref "R42") (pin "2") (pinfunction "2_2") (pintype "passive"))
      (node (ref "R45") (pin "1") (pinfunction "1_1") (pintype "passive"))
      (node (ref "U2") (pin "3") (pinfunction "GND_3") (pintype "power_in"))
      (node (ref "U2") (pin "7") (pinfunction "W_PAD_7") (pintype "power_in"))
      (node (ref "U3") (pin "3") (pinfunction "GND_3") (pintype "power_in"))
      (node (ref "U3") (pin "7") (pinfunction "W_PAD_7") (pintype "power_in"))
    )
    (net (code "11") (name "Net-(D1-Cathode)") (class "Default")
      (node (ref "C9") (pin "1") (pinfunction "1_1") (pintype "passive"))
      (node (ref "D1") (pin "C") (pinfunction "Cathode_C") (pintype "passive"))
      (node (ref "D3") (pin "C") (pinfunction "Cathode_C") (pintype "passive"))
      (node (ref "D5") (pin "5") (pinfunction "OUT_5") (pintype "power_in"))
      (node (ref "SW1") (pin "2") (pinfunction "COM-1_2") (pintype "passive"))
    )
    (net (code "12") (name "Net-(D2-Cathode)") (class "Default")
      (node (ref "D2") (pin "C") (pinfunction "Cathode_C") (pintype "passive"))
      (node (ref "SW1") (pin "5") (pinfunction "COM-2_5") (pintype "passive"))
    )
    (net (code "13") (name "Net-(D4-Vcc)") (class "Default")
      (node (ref "D4") (pin "5") (pinfunction "Vcc_5") (pintype "power_in"))
      (node (ref "F1") (pin "1") (pinfunction "1_1") (pintype "passive"))
      (node (ref "J2") (pin "A4B9") (pinfunction "VBUS_A4B9") (pintype "power_in"))
      (node (ref "J2") (pin "B4A9") (pinfunction "VBUS_B4A9") (pintype "power_in"))
    )
    (net (code "14") (name "Net-(D6-EN)") (class "Default")
      (node (ref "C18") (pin "1") (pinfunction "1_1") (pintype "passive"))
      (node (ref "D6") (pin "1") (pinfunction "VDD_1") (pintype "power_in"))
      (node (ref "D6") (pin "3") (pinfunction "EN_3") (pintype "input"))
      (node (ref "Q1") (pin "2") (pinfunction "S_2") (pintype "passive"))
    )
    (net (code "15") (name "Net-(D7-EN)") (class "Default")
      (node (ref "C19") (pin "1") (pinfunction "1_1") (pintype "passive"))
      (node (ref "D7") (pin "1") (pinfunction "VDD_1") (pintype "power_in"))
      (node (ref "D7") (pin "3") (pinfunction "EN_3") (pintype "input"))
      (node (ref "R225") (pin "2") (pinfunction "2_2") (pintype "passive"))
      (node (ref "R51") (pin "1") (pinfunction "1_1") (pintype "passive"))
      (node (ref "R52") (pin "1") (pinfunction "1_1") (pintype "passive"))
    )
    (net (code "16") (name "Net-(J2-CC1)") (class "Default")
      (node (ref "J2") (pin "A5") (pinfunction "CC1_A5") (pintype "power_in"))
      (node (ref "R40") (pin "2") (pinfunction "2_2") (pintype "passive"))
    )
    (net (code "17") (name "Net-(J2-CC2)") (class "Default")
      (node (ref "J2") (pin "B5") (pinfunction "CC2_B5") (pintype "power_in"))
      (node (ref "R39") (pin "2") (pinfunction "2_2") (pintype "passive"))
    )
    (net (code "18") (name "Net-(Q1-D)") (class "Default")
      (node (ref "BAT1") (pin "1") (pinfunction "1_1") (pintype "power_in"))
      (node (ref "D8") (pin "1") (pintype "passive"))
      (node (ref "Q1") (pin "3") (pinfunction "D_3") (pintype "passive"))
    )
    (net (code "19") (name "Net-(U2-EN)") (class "Default")
      (node (ref "C14") (pin "1") (pinfunction "1_1") (pintype "passive"))
      (node (ref "R32") (pin "1") (pinfunction "1_1") (pintype "passive"))
      (node (ref "R33") (pin "2") (pinfunction "2_2") (pintype "passive"))
      (node (ref "U2") (pin "2") (pinfunction "EN_2") (pintype "input"))
    )
    (net (code "20") (name "Net-(U2-IN)") (class "Default")
      (node (ref "C6") (pin "1") (pinfunction "1_1") (pintype "passive"))
      (node (ref "C68") (pin "1") (pinfunction "1_1") (pintype "passive"))
      (node (ref "R29") (pin "2") (pinfunction "2_2") (pintype "passive"))
      (node (ref "R32") (pin "2") (pinfunction "2_2") (pintype "passive"))
      (node (ref "U2") (pin "1") (pinfunction "IN_1") (pintype "input"))
    )
    (net (code "21") (name "Net-(U2-PG)") (class "Default")
      (node (ref "R31") (pin "1") (pinfunction "1_1") (pintype "passive"))
      (node (ref "U2") (pin "4") (pinfunction "PG_4") (pintype "open_collector"))
    )
    (net (code "22") (name "Net-(U2-SNS)") (class "Default")
      (node (ref "R30") (pin "1") (pinfunction "1_1") (pintype "passive"))
      (node (ref "R34") (pin "2") (pinfunction "2_2") (pintype "passive"))
      (node (ref "U2") (pin "5") (pinfunction "SNS_5") (pintype "input"))
    )
    (net (code "23") (name "Net-(U3-EN)") (class "Default")
      (node (ref "C15") (pin "2") (pinfunction "2_2") (pintype "passive"))
      (node (ref "R201") (pin "2") (pinfunction "2_2") (pintype "passive"))
      (node (ref "R35") (pin "1") (pinfunction "1_1") (pintype "passive"))
      (node (ref "U3") (pin "2") (pinfunction "EN_2") (pintype "input"))
    )
    (net (code "24") (name "Net-(U3-IN)") (class "Default")
      (node (ref "C13") (pin "1") (pinfunction "1_1") (pintype "passive"))
      (node (ref "C70") (pin "1") (pinfunction "1_1") (pintype "passive"))
      (node (ref "R35") (pin "2") (pinfunction "2_2") (pintype "passive"))
      (node (ref "R41") (pin "2") (pinfunction "2_2") (pintype "passive"))
      (node (ref "U3") (pin "1") (pinfunction "IN_1") (pintype "input"))
    )
    (net (code "25") (name "Net-(U3-PG)") (class "Default")
      (node (ref "R43") (pin "1") (pinfunction "1_1") (pintype "passive"))
      (node (ref "U3") (pin "4") (pinfunction "PG_4") (pintype "open_collector"))
    )
    (net (code "26") (name "Net-(U3-SNS)") (class "Default")
      (node (ref "R44") (pin "1") (pinfunction "1_1") (pintype "passive"))
      (node (ref "R45") (pin "2") (pinfunction "2_2") (pintype "passive"))
      (node (ref "U3") (pin "5") (pinfunction "SNS_5") (pintype "input"))
    )
    (net (code "27") (name "VBUS") (class "Default")
      (node (ref "R29") (pin "1") (pinfunction "1_1") (pintype "passive"))
      (node (ref "R38") (pin "1") (pinfunction "1_1") (pintype "passive"))
      (node (ref "R41") (pin "1") (pinfunction "1_1") (pintype "passive"))
      (node (ref "SW1") (pin "1") (pinfunction "N.O-1_1") (pintype "passive"))
    )
    (net (code "28") (name "VDD") (class "Default")
      (node (ref "J3") (pin "2") (pinfunction "2_2") (pintype "passive"))
      (node (ref "R46") (pin "1") (pinfunction "1_1") (pintype "passive"))
      (node (ref "S1") (pin "4") (pintype "passive"))
    )
    (net (code "29") (name "VDDIO_Periph") (class "Default")
      (node (ref "R199") (pin "2") (pinfunction "2_2") (pintype "passive"))
      (node (ref "S1") (pin "3") (pintype "passive"))
    )
    (net (code "30") (name "VDD_M") (class "Default")
      (node (ref "J3") (pin "3") (pinfunction "3_3") (pintype "passive"))
      (node (ref "R199") (pin "1") (pinfunction "1_1") (pintype "passive"))
      (node (ref "R37") (pin "1") (pinfunction "1_1") (pintype "passive"))
      (node (ref "R46") (pin "2") (pinfunction "2_2") (pintype "passive"))
      (node (ref "S1") (pin "1") (pinfunction "1_1") (pintype "passive"))
      (node (ref "S1") (pin "2") (pinfunction "2_2") (pintype "passive"))
      (node (ref "SW2") (pin "2") (pinfunction "COM-1_2") (pintype "passive"))
    )
    (net (code "31") (name "V_Coin_Cell") (class "Default")
      (node (ref "D6") (pin "5") (pinfunction "OUT_5") (pintype "power_in"))
      (node (ref "D7") (pin "5") (pinfunction "OUT_5") (pintype "power_in"))
      (node (ref "R225") (pin "1") (pinfunction "1_1") (pintype "passive"))
      (node (ref "R37") (pin "2") (pinfunction "2_2") (pintype "passive"))
      (node (ref "SW2") (pin "1") (pinfunction "N.O-1_1") (pintype "passive"))
    )
    (net (code "32") (name "unconnected-(D4-IO3-Pad4)") (class "Default")
      (node (ref "D4") (pin "4") (pinfunction "IO3_4") (pintype "passive+no_connect"))
    )
    (net (code "33") (name "unconnected-(D5-NC-Pad4)") (class "Default")
      (node (ref "D5") (pin "4") (pinfunction "NC_4") (pintype "passive+no_connect"))
    )
    (net (code "34") (name "unconnected-(D6-NC-Pad4)") (class "Default")
      (node (ref "D6") (pin "4") (pinfunction "NC_4") (pintype "passive+no_connect"))
    )
    (net (code "35") (name "unconnected-(D7-NC-Pad4)") (class "Default")
      (node (ref "D7") (pin "4") (pinfunction "NC_4") (pintype "passive+no_connect"))
    )
    (net (code "36") (name "unconnected-(J2-SBU1-PadA8)") (class "Default")
      (node (ref "J2") (pin "A8") (pinfunction "SBU1_A8") (pintype "power_in+no_connect"))
    )
    (net (code "37") (name "unconnected-(J2-SBU2-PadB8)") (class "Default")
      (node (ref "J2") (pin "B8") (pinfunction "SBU2_B8") (pintype "power_in+no_connect"))
    )
    (net (code "38") (name "unconnected-(SW1-N.C-1-Pad3)") (class "Default")
      (node (ref "SW1") (pin "3") (pinfunction "N.C-1_3") (pintype "passive+no_connect"))
    )
    (net (code "39") (name "unconnected-(SW1-N.C-2-Pad6)") (class "Default")
      (node (ref "SW1") (pin "6") (pinfunction "N.C-2_6") (pintype "passive+no_connect"))
    )
    (net (code "40") (name "unconnected-(SW2-COM-2-Pad5)") (class "Default")
      (node (ref "SW2") (pin "5") (pinfunction "COM-2_5") (pintype "passive+no_connect"))
    )
    (net (code "41") (name "unconnected-(SW2-N.C-2-Pad6)") (class "Default")
      (node (ref "SW2") (pin "6") (pinfunction "N.C-2_6") (pintype "passive+no_connect"))
    )
    (net (code "42") (name "unconnected-(SW2-N.O-2-Pad4)") (class "Default")
      (node (ref "SW2") (pin "4") (pinfunction "N.O-2_4") (pintype "passive+no_connect"))
    )
  )
)
